# Conectores.net
KiCad netlist of a schematic drawn in Altium Designer
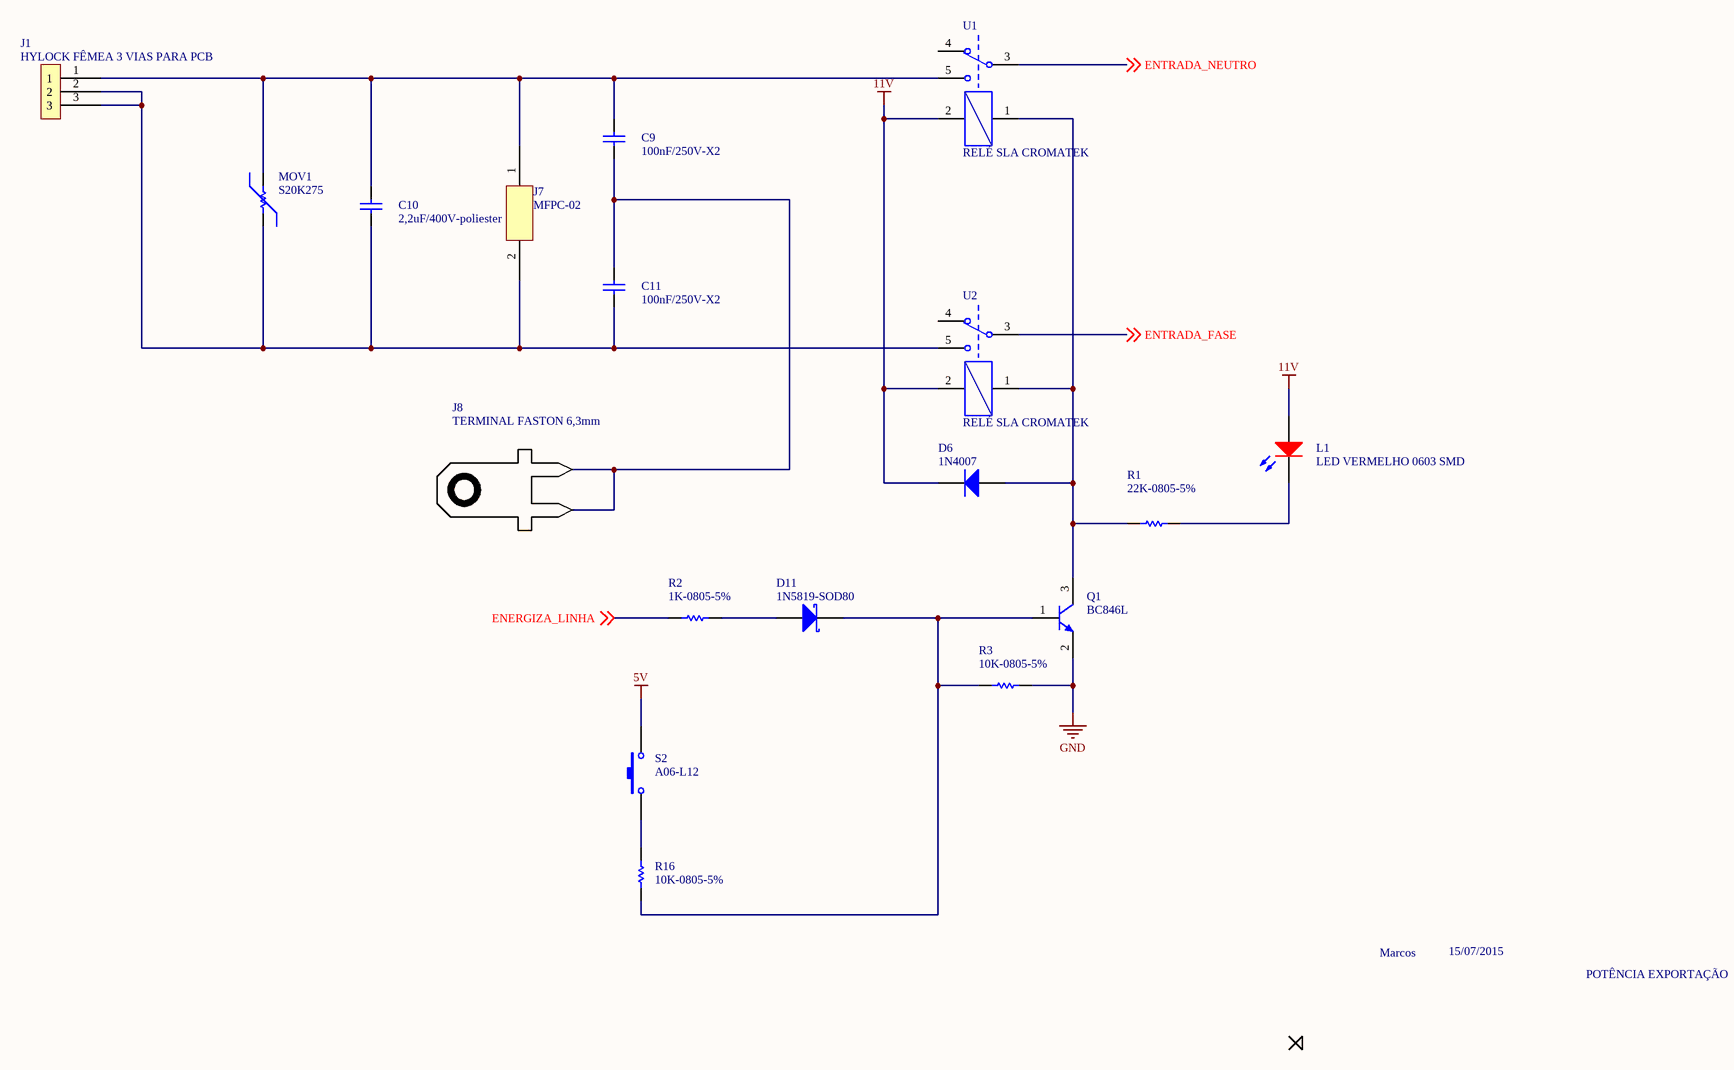
[diagram p0: Conectores.SchDoc]

(export (version "E")
  (design (tool "Eeschema 10.0.6"))
  (components
    (comp (ref "C9")
      (value "100nF/250V-X2")
      (footprint "CAP-250V-PS")
      (description "100nF/50V-0805")
      (libsource (lib "AquinoLib") (part "100nF/50-0805-NPO"))
    )
    (comp (ref "C10")
      (value "2,2uF/400V-poliester")
      (footprint "CAPACITOR H4")
      (description "100nF/50V-0805")
      (libsource (lib "AquinoLib") (part "100nF/50-0805-NPO"))
    )
    (comp (ref "C11")
      (value "100nF/250V-X2")
      (footprint "CAP-250V-PS")
      (description "100nF/50V-0805")
      (libsource (lib "AquinoLib") (part "100nF/50-0805-NPO"))
    )
    (comp (ref "D6") (value "1N4007") (footprint "SMA DIODES") (libsource (lib "AquinoLib") (part "1N4007")))
    (comp (ref "D11")
      (value "1N5819-SOD80")
      (footprint "MINIMLEF/SOD80 - REVISADO ONDA")
      (libsource (lib "AquinoLib") (part "1N5819-SOD80"))
    )
    (comp (ref "J1")
      (value "HYLOCK FÊMEA 3 VIAS PARA PCB")
      (footprint "CONECTOR HYLOCK 3 VIAS")
      (description "PCMC2-3")
      (libsource (lib "AquinoLib") (part "PCMC2-3"))
    )
    (comp (ref "J7")
      (value "MFPC-02")
      (footprint "MFPC-02")
      (description "MFPL-02")
      (libsource (lib "AquinoLib") (part "MFPL-02"))
    )
    (comp (ref "J8")
      (value "TERMINAL FASTON 6,3mm")
      (footprint "TERMINAL FASTON")
      (libsource (lib "AquinoLib") (part "TERMINAL FASTON 6,3mm"))
    )
    (comp (ref "L1")
      (value "LED VERMELHO 0603 SMD")
      (footprint "LED 1206")
      (libsource (lib "AquinoLib") (part "LED VERMELHO 0603 SMD"))
    )
    (comp (ref "MOV1")
      (value "S20K275")
      (footprint "VARISTOR 20mm")
      (libsource (lib "AquinoLib") (part "S20K275"))
    )
    (comp (ref "Q1")
      (value "BC846L")
      (footprint "SOT23 - REVISADO ONDA")
      (libsource (lib "AquinoLib") (part "BC846"))
    )
    (comp (ref "R1")
      (value "22K-0805-5%")
      (footprint "0805-REVISADO ONDA")
      (libsource (lib "AquinoLib") (part "22K-0805-5%"))
    )
    (comp (ref "R2")
      (value "1K-0805-5%")
      (footprint "0805-REVISADO ONDA")
      (description "10K-0805-5%")
      (libsource (lib "AquinoLib") (part "10K-0805-5%"))
    )
    (comp (ref "R3")
      (value "10K-0805-5%")
      (footprint "0805-REVISADO ONDA")
      (libsource (lib "AquinoLib") (part "10K-0805-5%"))
    )
    (comp (ref "R16")
      (value "10K-0805-5%")
      (footprint "0805-REVISADO ONDA")
      (description "1K-0805-5%")
      (libsource (lib "AquinoLib") (part "1K-0805-5%"))
    )
    (comp (ref "S2")
      (value "A06-L12")
      (footprint "CHAVE_A06")
      (libsource (lib "ChaveDigital3") (part "A06-L12"))
    )
    (comp (ref "U1")
      (value "RELÉ SLA CROMATEK")
      (footprint "RELE SLA CROMATEK")
      (libsource (lib "AquinoLib") (part "RELÉ SLA CROMATEK"))
    )
    (comp (ref "U2")
      (value "RELÉ SLA CROMATEK")
      (footprint "RELE SLA CROMATEK")
      (libsource (lib "AquinoLib") (part "RELÉ SLA CROMATEK"))
    )
  )
  (nets
    (net (code "1") (name "5V") (class "Default")
      (node (ref "S2") (pin "2") (pinfunction "2_2") (pintype "passive"))
    )
    (net (code "2") (name "11V") (class "Default")
      (node (ref "D6") (pin "2") (pinfunction "K_2") (pintype "passive"))
      (node (ref "L1") (pin "1") (pinfunction "A_1") (pintype "passive"))
      (node (ref "U1") (pin "2") (pinfunction "A2_2") (pintype "passive"))
      (node (ref "U2") (pin "2") (pinfunction "A2_2") (pintype "passive"))
    )
    (net (code "3") (name "ENERGIZA_LINHA") (class "Default")
      (node (ref "R2") (pin "1") (pinfunction "1_1") (pintype "passive"))
    )
    (net (code "4") (name "ENTRADA_FASE") (class "Default")
      (node (ref "U2") (pin "3") (pinfunction "3_3") (pintype "passive"))
    )
    (net (code "5") (name "ENTRADA_NEUTRO") (class "Default")
      (node (ref "U1") (pin "3") (pinfunction "3_3") (pintype "passive"))
    )
    (net (code "6") (name "GND") (class "Default")
      (node (ref "Q1") (pin "2") (pinfunction "E_2") (pintype "passive"))
      (node (ref "R3") (pin "2") (pinfunction "2_2") (pintype "passive"))
    )
    (net (code "7") (name "Net-(C10-Pad1)") (class "Default")
      (node (ref "C10") (pin "1") (pinfunction "1_1") (pintype "passive"))
      (node (ref "C11") (pin "1") (pinfunction "1_1") (pintype "passive"))
      (node (ref "J1") (pin "2") (pinfunction "2_2") (pintype "passive"))
      (node (ref "J1") (pin "3") (pinfunction "3_3") (pintype "passive"))
      (node (ref "J7") (pin "2") (pinfunction "2_2") (pintype "passive"))
      (node (ref "MOV1") (pin "1") (pinfunction "1_1") (pintype "passive"))
      (node (ref "U2") (pin "5") (pinfunction "5_5") (pintype "passive"))
    )
    (net (code "8") (name "Net-(C10-Pad2)") (class "Default")
      (node (ref "C10") (pin "2") (pinfunction "2_2") (pintype "passive"))
      (node (ref "C9") (pin "2") (pinfunction "2_2") (pintype "passive"))
      (node (ref "J1") (pin "1") (pinfunction "1_1") (pintype "passive"))
      (node (ref "J7") (pin "1") (pinfunction "1_1") (pintype "passive"))
      (node (ref "MOV1") (pin "2") (pinfunction "2_2") (pintype "passive"))
      (node (ref "U1") (pin "5") (pinfunction "5_5") (pintype "passive"))
    )
    (net (code "9") (name "Net-(C11-Pad2)") (class "Default")
      (node (ref "C11") (pin "2") (pinfunction "2_2") (pintype "passive"))
      (node (ref "C9") (pin "1") (pinfunction "1_1") (pintype "passive"))
      (node (ref "J8") (pin "1") (pinfunction "1_1") (pintype "passive"))
      (node (ref "J8") (pin "2") (pinfunction "2_2") (pintype "passive"))
    )
    (net (code "10") (name "Net-(D6-A)") (class "Default")
      (node (ref "D6") (pin "1") (pinfunction "A_1") (pintype "passive"))
      (node (ref "Q1") (pin "3") (pinfunction "C_3") (pintype "passive"))
      (node (ref "R1") (pin "1") (pinfunction "1_1") (pintype "passive"))
      (node (ref "U1") (pin "1") (pinfunction "A1_1") (pintype "passive"))
      (node (ref "U2") (pin "1") (pinfunction "A1_1") (pintype "passive"))
    )
    (net (code "11") (name "Net-(D11-A)") (class "Default")
      (node (ref "D11") (pin "1") (pinfunction "A_1") (pintype "passive"))
      (node (ref "R2") (pin "2") (pinfunction "2_2") (pintype "passive"))
    )
    (net (code "12") (name "Net-(D11-K)") (class "Default")
      (node (ref "D11") (pin "2") (pinfunction "K_2") (pintype "passive"))
      (node (ref "Q1") (pin "1") (pinfunction "B_1") (pintype "passive"))
      (node (ref "R16") (pin "1") (pinfunction "1_1") (pintype "passive"))
      (node (ref "R3") (pin "1") (pinfunction "1_1") (pintype "passive"))
    )
    (net (code "13") (name "Net-(L1-K)") (class "Default")
      (node (ref "L1") (pin "2") (pinfunction "K_2") (pintype "passive"))
      (node (ref "R1") (pin "2") (pinfunction "2_2") (pintype "passive"))
    )
    (net (code "14") (name "Net-(R16-Pad2)") (class "Default")
      (node (ref "R16") (pin "2") (pinfunction "2_2") (pintype "passive"))
      (node (ref "S2") (pin "1") (pinfunction "1_1") (pintype "passive"))
    )
    (net (code "15") (name "unconnected-(U1-Pad4)") (class "Default")
      (node (ref "U1") (pin "4") (pinfunction "4_4") (pintype "passive"))
    )
    (net (code "16") (name "unconnected-(U2-Pad4)") (class "Default")
      (node (ref "U2") (pin "4") (pinfunction "4_4") (pintype "passive"))
    )
  )
)
